# GSM_On-Off_Control.net
KiCad netlist of a schematic drawn in Altium Designer
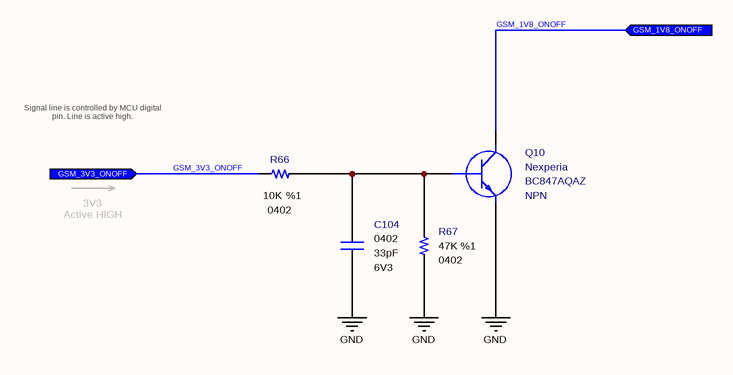
[diagram p0: GSM On-Off Control.SchDoc]

(export (version "E")
  (design (tool "Eeschema 10.0.6"))
  (components
    (comp (ref "C104")
      (value "33pF")
      (footprint "CAPACITOR_0402")
      (description "Capacitor - 33pF [0402] (Ceramic)")
      (fields
        (field (name "CASE") "0402")
        (field (name "TOLERANCE") "10%")
        (field (name "VOLTAGE") "6V3")
        (field (name "MANUFACTURER PART NUMBER") "C0402C330J9RACAUTO")
      )
      (libsource (lib "Ovoo_Library") (part "Capacitor - 33pF [0402-6V3]"))
    )
    (comp (ref "Q10")
      (value "BC847AQAZ")
      (footprint "SOT1215")
      (description "Bipolar NPN Transistors")
      (fields
        (field (name "POLARITY") "NPN")
        (field (name "MANUFACTURER NAME") "Nexperia")
        (field (name "MANUFACTURER PART NUMBER") "BC847AQAZ")
      )
      (libsource (lib "Ovoo_Library") (part "Transistor - BC847"))
    )
    (comp (ref "R66")
      (value "10K")
      (footprint "RESISTOR_0402")
      (description "Thick Film Resistors - SMD 1/16 W 10 Kohms 1%")
      (fields
        (field (name "TOLERANCE") "%1")
        (field (name "CASE") "0402")
        (field (name "MANUFACTURER PART NUMBER") "CRCW040210K0FKED")
        (field (name "MOUSER PART NUMBER") "71-CRCW0402-10K-E3")
      )
      (libsource (lib "Ovoo_Library") (part "Resistor - 10K"))
    )
    (comp (ref "R67")
      (value "47K")
      (footprint "RESISTOR_0402")
      (description "Thick Film Resistors - SMD 1/16 W 47 Kohms 1%")
      (fields
        (field (name "TOLERANCE") "%1")
        (field (name "CASE") "0402")
        (field (name "MANUFACTURER PART NUMBER") "CRCW040247K0FKED")
        (field (name "Comment") "47K - 0402 - %1 - 1/16W")
      )
      (libsource (lib "Ovoo_Library") (part "Resistor - 47K"))
    )
  )
  (nets
    (net (code "1") (name "/GSM_1V8_ONOFF") (class "Default")
      (node (ref "Q10") (pin "3") (pinfunction "C_3") (pintype "passive"))
    )
    (net (code "2") (name "/GSM_3V3_ONOFF") (class "Default")
      (node (ref "R66") (pin "2") (pinfunction "2_2") (pintype "passive"))
    )
    (net (code "3") (name "GND") (class "Default")
      (node (ref "C104") (pin "2") (pinfunction "2_2") (pintype "passive"))
      (node (ref "Q10") (pin "2") (pinfunction "E_2") (pintype "passive"))
      (node (ref "R67") (pin "1") (pinfunction "1_1") (pintype "passive"))
    )
    (net (code "4") (name "Net-(Q10-B)") (class "Default")
      (node (ref "C104") (pin "1") (pinfunction "1_1") (pintype "passive"))
      (node (ref "Q10") (pin "1") (pinfunction "B_1") (pintype "passive"))
      (node (ref "R66") (pin "1") (pinfunction "1_1") (pintype "passive"))
      (node (ref "R67") (pin "2") (pinfunction "2_2") (pintype "passive"))
    )
  )
)
